# LM2596.net
KiCad netlist of a schematic drawn in Altium Designer
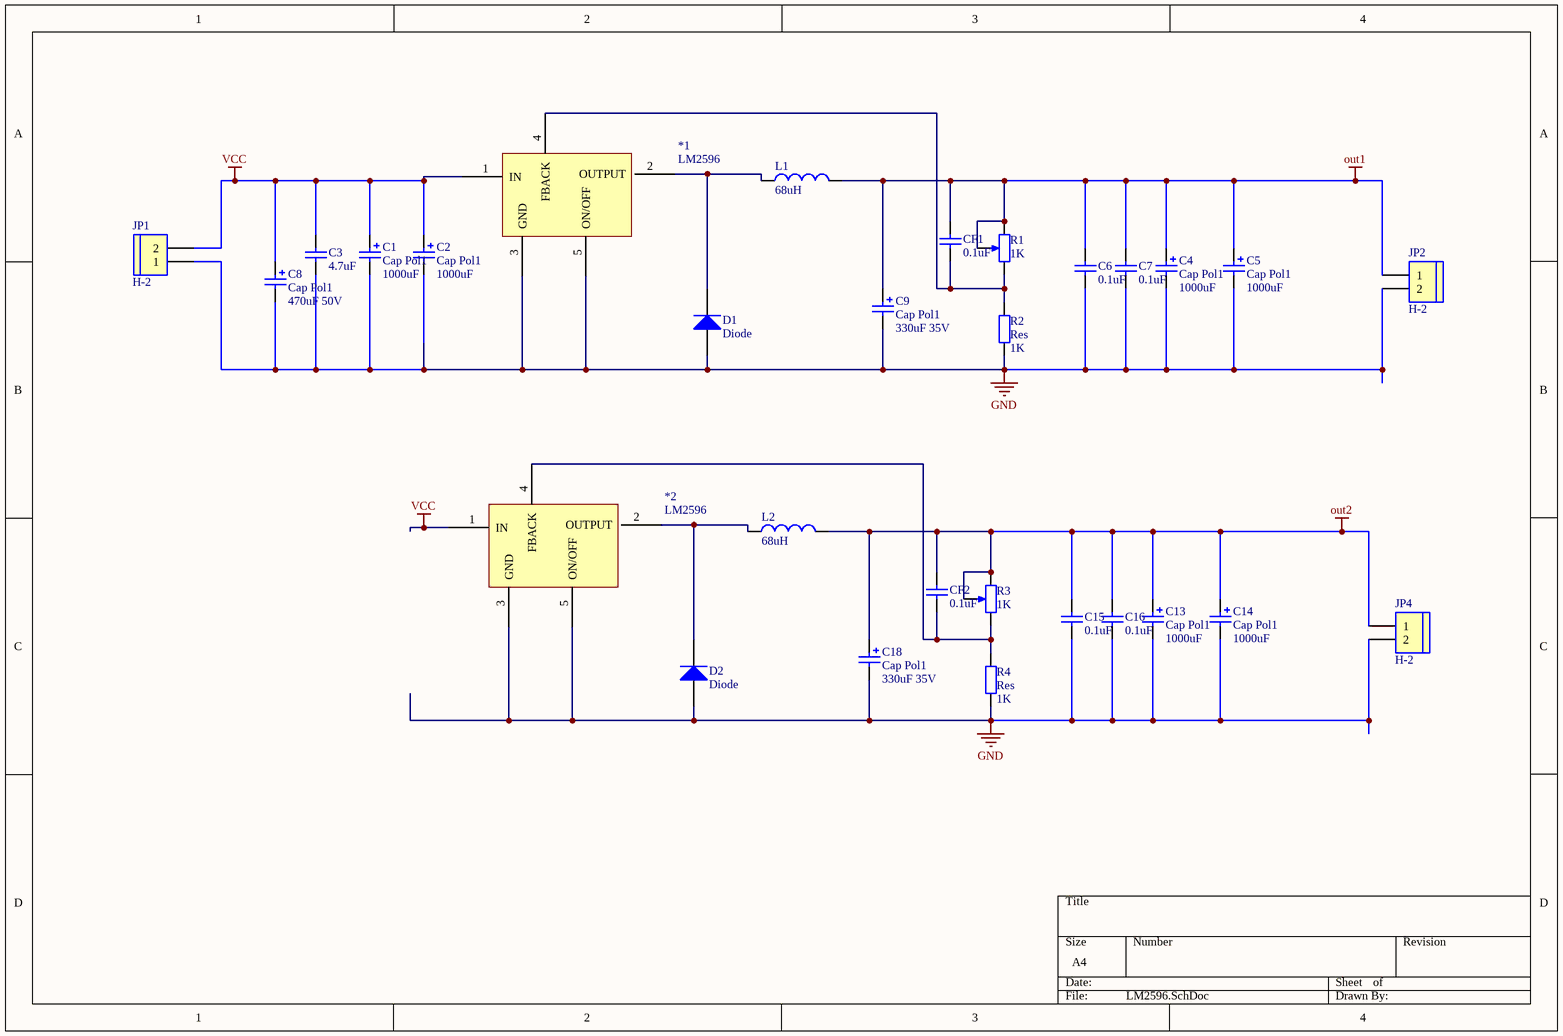
[diagram p0: LM2596.SchDoc]

(export (version "E")
  (design (tool "Eeschema 10.0.6"))
  (components
    (comp (ref "*1") (value "LM2596") (footprint "HDR1-5") (libsource (lib "HGH") (part "LM2596")))
    (comp (ref "*2") (value "LM2596") (footprint "HDR1-5") (libsource (lib "HGH") (part "LM2596")))
    (comp (ref "C1")
      (value "Cap Pol1")
      (footprint "RB0.3-0.65")
      (description "Polarized Capacitor (Radial)")
      (fields
        (field (name "MANUFACTURER") "Generic Components")
        (field (name "ALTIUM_VALUE") "1000uF")
        (field (name "PUBLISHER") "Altium Hobart Technology Centre")
      )
      (libsource (lib "HGH") (part "Cap Pol1"))
    )
    (comp (ref "C2")
      (value "Cap Pol1")
      (footprint "RB0.3-0.65")
      (description "Polarized Capacitor (Radial)")
      (fields
        (field (name "MANUFACTURER") "Generic Components")
        (field (name "ALTIUM_VALUE") "1000uF")
        (field (name "PUBLISHER") "Altium Hobart Technology Centre")
      )
      (libsource (lib "HGH") (part "Cap Pol1"))
    )
    (comp (ref "C3")
      (value "4.7uF")
      (footprint "CC1005-0402")
      (description "Capacitor")
      (fields
        (field (name "MANUFACTURER") "Generic Components")
        (field (name "Comment") "CAP")
        (field (name "PUBLISHER") "Altium Hobart Technology Centre")
      )
      (libsource (lib "HGH") (part "CAP"))
    )
    (comp (ref "C4")
      (value "Cap Pol1")
      (footprint "RB0.3-0.65")
      (description "Polarized Capacitor (Radial)")
      (fields
        (field (name "MANUFACTURER") "Generic Components")
        (field (name "ALTIUM_VALUE") "1000uF")
        (field (name "PUBLISHER") "Altium Hobart Technology Centre")
      )
      (libsource (lib "HGH") (part "Cap Pol1"))
    )
    (comp (ref "C5")
      (value "Cap Pol1")
      (footprint "RB0.3-0.65")
      (description "Polarized Capacitor (Radial)")
      (fields
        (field (name "MANUFACTURER") "Generic Components")
        (field (name "ALTIUM_VALUE") "1000uF")
        (field (name "PUBLISHER") "Altium Hobart Technology Centre")
      )
      (libsource (lib "HGH") (part "Cap Pol1"))
    )
    (comp (ref "C6")
      (value "0.1uF")
      (footprint "CC1005-0402")
      (description "Capacitor")
      (fields
        (field (name "MANUFACTURER") "Generic Components")
        (field (name "Comment") "CAP")
        (field (name "PUBLISHER") "Altium Hobart Technology Centre")
      )
      (libsource (lib "HGH") (part "CAP"))
    )
    (comp (ref "C7")
      (value "0.1uF")
      (footprint "CC1005-0402")
      (description "Capacitor")
      (fields
        (field (name "MANUFACTURER") "Generic Components")
        (field (name "Comment") "CAP")
        (field (name "PUBLISHER") "Altium Hobart Technology Centre")
      )
      (libsource (lib "HGH") (part "CAP"))
    )
    (comp (ref "C8")
      (value "Cap Pol1")
      (footprint "RB0.3-0.65")
      (description "Polarized Capacitor (Radial)")
      (fields
        (field (name "MANUFACTURER") "Generic Components")
        (field (name "ALTIUM_VALUE") "470uF 50V")
        (field (name "PUBLISHER") "Altium Hobart Technology Centre")
      )
      (libsource (lib "HGH") (part "Cap Pol1"))
    )
    (comp (ref "C9")
      (value "Cap Pol1")
      (footprint "RB0.3-0.65")
      (description "Polarized Capacitor (Radial)")
      (fields
        (field (name "MANUFACTURER") "Generic Components")
        (field (name "ALTIUM_VALUE") "330uF 35V")
        (field (name "PUBLISHER") "Altium Hobart Technology Centre")
      )
      (libsource (lib "HGH") (part "Cap Pol1"))
    )
    (comp (ref "C13")
      (value "Cap Pol1")
      (footprint "RB0.3-0.65")
      (description "Polarized Capacitor (Radial)")
      (fields
        (field (name "MANUFACTURER") "Generic Components")
        (field (name "ALTIUM_VALUE") "1000uF")
        (field (name "PUBLISHER") "Altium Hobart Technology Centre")
      )
      (libsource (lib "HGH") (part "Cap Pol1"))
    )
    (comp (ref "C14")
      (value "Cap Pol1")
      (footprint "RB0.3-0.65")
      (description "Polarized Capacitor (Radial)")
      (fields
        (field (name "MANUFACTURER") "Generic Components")
        (field (name "ALTIUM_VALUE") "1000uF")
        (field (name "PUBLISHER") "Altium Hobart Technology Centre")
      )
      (libsource (lib "HGH") (part "Cap Pol1"))
    )
    (comp (ref "C15")
      (value "0.1uF")
      (footprint "CC1005-0402")
      (description "Capacitor")
      (fields
        (field (name "MANUFACTURER") "Generic Components")
        (field (name "Comment") "CAP")
        (field (name "PUBLISHER") "Altium Hobart Technology Centre")
      )
      (libsource (lib "HGH") (part "CAP"))
    )
    (comp (ref "C16")
      (value "0.1uF")
      (footprint "CC1005-0402")
      (description "Capacitor")
      (fields
        (field (name "MANUFACTURER") "Generic Components")
        (field (name "Comment") "CAP")
        (field (name "PUBLISHER") "Altium Hobart Technology Centre")
      )
      (libsource (lib "HGH") (part "CAP"))
    )
    (comp (ref "C18")
      (value "Cap Pol1")
      (footprint "RB0.3-0.65")
      (description "Polarized Capacitor (Radial)")
      (fields
        (field (name "MANUFACTURER") "Generic Components")
        (field (name "ALTIUM_VALUE") "330uF 35V")
        (field (name "PUBLISHER") "Altium Hobart Technology Centre")
      )
      (libsource (lib "HGH") (part "Cap Pol1"))
    )
    (comp (ref "CF1")
      (value "0.1uF")
      (footprint "CC1005-0402")
      (description "Capacitor")
      (fields
        (field (name "MANUFACTURER") "Generic Components")
        (field (name "Comment") "CAP")
        (field (name "PUBLISHER") "Altium Hobart Technology Centre")
      )
      (libsource (lib "HGH") (part "CAP"))
    )
    (comp (ref "CF2")
      (value "0.1uF")
      (footprint "CC1005-0402")
      (description "Capacitor")
      (fields
        (field (name "MANUFACTURER") "Generic Components")
        (field (name "Comment") "CAP")
        (field (name "PUBLISHER") "Altium Hobart Technology Centre")
      )
      (libsource (lib "HGH") (part "CAP"))
    )
    (comp (ref "D1")
      (value "Diode")
      (footprint "Diode-5817")
      (description "Default Diode")
      (fields
        (field (name "MANUFACTURER") "Generic Components")
        (field (name "PUBLISHER") "Altium Hobart Technology Centre")
      )
      (libsource (lib "HGH") (part "Diode"))
    )
    (comp (ref "D2")
      (value "Diode")
      (footprint "Diode-5817")
      (description "Default Diode")
      (fields
        (field (name "MANUFACTURER") "Generic Components")
        (field (name "PUBLISHER") "Altium Hobart Technology Centre")
      )
      (libsource (lib "HGH") (part "Diode"))
    )
    (comp (ref "JP1")
      (value "H-2")
      (footprint "JP-2")
      (description "Header, 2-Pin")
      (fields (field (name "MANUFACTURER") "Generic Components"))
      (libsource (lib "") (part "H-2_1"))
    )
    (comp (ref "JP2")
      (value "H-2")
      (footprint "JP-2")
      (description "Header, 2-Pin")
      (fields (field (name "MANUFACTURER") "Generic Components"))
      (libsource (lib "HGH") (part "H-2"))
    )
    (comp (ref "JP4")
      (value "H-2")
      (footprint "JP-2")
      (description "Header, 2-Pin")
      (fields (field (name "MANUFACTURER") "Generic Components"))
      (libsource (lib "HGH") (part "H-2"))
    )
    (comp (ref "L1")
      (value "68uH")
      (footprint "RBL0.2")
      (description "Inductor")
      (fields
        (field (name "MANUFACTURER") "Generic Components")
        (field (name "Comment") "INDUCTOT")
        (field (name "PUBLISHER") "Altium Hobart Technology Centre")
      )
      (libsource (lib "HGH") (part "INDUCTOT"))
    )
    (comp (ref "L2")
      (value "68uH")
      (footprint "RBL0.2")
      (description "Inductor")
      (fields
        (field (name "MANUFACTURER") "Generic Components")
        (field (name "Comment") "INDUCTOT")
        (field (name "PUBLISHER") "Altium Hobart Technology Centre")
      )
      (libsource (lib "HGH") (part "INDUCTOT"))
    )
    (comp (ref "R1")
      (value "1K")
      (footprint "VR-S")
      (description "Potentiometer")
      (fields (field (name "Comment") "RES-Pot2"))
      (libsource (lib "HGH") (part "RES-Pot2"))
    )
    (comp (ref "R2")
      (value "Res")
      (footprint "1n4148")
      (description "Resistor")
      (fields
        (field (name "MANUFACTURER") "Generic Components")
        (field (name "ALTIUM_VALUE") "1K")
        (field (name "PUBLISHER") "Altium Hobart Technology Centre")
      )
      (libsource (lib "HGH") (part "Res"))
    )
    (comp (ref "R3")
      (value "1K")
      (footprint "VR-S")
      (description "Potentiometer")
      (fields (field (name "Comment") "RES-Pot2"))
      (libsource (lib "HGH") (part "RES-Pot2"))
    )
    (comp (ref "R4")
      (value "Res")
      (footprint "1n4148")
      (description "Resistor")
      (fields
        (field (name "MANUFACTURER") "Generic Components")
        (field (name "ALTIUM_VALUE") "1K")
        (field (name "PUBLISHER") "Altium Hobart Technology Centre")
      )
      (libsource (lib "HGH") (part "Res"))
    )
  )
  (nets
    (net (code "1") (name "GND") (class "Default")
      (node (ref "*1") (pin "3") (pinfunction "GND_3") (pintype "passive"))
      (node (ref "*1") (pin "5") (pinfunction "ON/OFF_5") (pintype "passive"))
      (node (ref "*2") (pin "3") (pinfunction "GND_3") (pintype "passive"))
      (node (ref "*2") (pin "5") (pinfunction "ON/OFF_5") (pintype "passive"))
      (node (ref "C1") (pin "2") (pinfunction "2_2") (pintype "passive"))
      (node (ref "C13") (pin "2") (pinfunction "2_2") (pintype "passive"))
      (node (ref "C14") (pin "2") (pinfunction "2_2") (pintype "passive"))
      (node (ref "C15") (pin "1") (pinfunction "1_1") (pintype "passive"))
      (node (ref "C16") (pin "1") (pinfunction "1_1") (pintype "passive"))
      (node (ref "C18") (pin "2") (pinfunction "2_2") (pintype "passive"))
      (node (ref "C2") (pin "2") (pinfunction "2_2") (pintype "passive"))
      (node (ref "C3") (pin "1") (pinfunction "1_1") (pintype "passive"))
      (node (ref "C4") (pin "2") (pinfunction "2_2") (pintype "passive"))
      (node (ref "C5") (pin "2") (pinfunction "2_2") (pintype "passive"))
      (node (ref "C6") (pin "1") (pinfunction "1_1") (pintype "passive"))
      (node (ref "C7") (pin "1") (pinfunction "1_1") (pintype "passive"))
      (node (ref "C8") (pin "2") (pinfunction "2_2") (pintype "passive"))
      (node (ref "C9") (pin "2") (pinfunction "2_2") (pintype "passive"))
      (node (ref "D1") (pin "1") (pinfunction "A_1") (pintype "passive"))
      (node (ref "D2") (pin "1") (pinfunction "A_1") (pintype "passive"))
      (node (ref "JP1") (pin "1") (pinfunction "1_1") (pintype "passive"))
      (node (ref "JP2") (pin "2") (pinfunction "2_2") (pintype "passive"))
      (node (ref "JP4") (pin "2") (pinfunction "2_2") (pintype "passive"))
      (node (ref "R2") (pin "1") (pinfunction "1_1") (pintype "passive"))
      (node (ref "R4") (pin "1") (pinfunction "1_1") (pintype "passive"))
    )
    (net (code "2") (name "Net-(*1-FBACK)") (class "Default")
      (node (ref "*1") (pin "4") (pinfunction "FBACK_4") (pintype "passive"))
      (node (ref "CF1") (pin "1") (pinfunction "1_1") (pintype "passive"))
      (node (ref "R1") (pin "1") (pinfunction "BOT_1") (pintype "passive"))
      (node (ref "R2") (pin "2") (pinfunction "2_2") (pintype "passive"))
    )
    (net (code "3") (name "Net-(*1-OUTPUT)") (class "Default")
      (node (ref "*1") (pin "2") (pinfunction "OUTPUT_2") (pintype "passive"))
      (node (ref "D1") (pin "2") (pinfunction "K_2") (pintype "passive"))
      (node (ref "L1") (pin "1") (pinfunction "1_1") (pintype "passive"))
    )
    (net (code "4") (name "Net-(*2-FBACK)") (class "Default")
      (node (ref "*2") (pin "4") (pinfunction "FBACK_4") (pintype "passive"))
      (node (ref "CF2") (pin "1") (pinfunction "1_1") (pintype "passive"))
      (node (ref "R3") (pin "1") (pinfunction "BOT_1") (pintype "passive"))
      (node (ref "R4") (pin "2") (pinfunction "2_2") (pintype "passive"))
    )
    (net (code "5") (name "Net-(*2-OUTPUT)") (class "Default")
      (node (ref "*2") (pin "2") (pinfunction "OUTPUT_2") (pintype "passive"))
      (node (ref "D2") (pin "2") (pinfunction "K_2") (pintype "passive"))
      (node (ref "L2") (pin "1") (pinfunction "1_1") (pintype "passive"))
    )
    (net (code "6") (name "VCC") (class "Default")
      (node (ref "*1") (pin "1") (pinfunction "IN_1") (pintype "passive"))
      (node (ref "*2") (pin "1") (pinfunction "IN_1") (pintype "passive"))
      (node (ref "C1") (pin "1") (pinfunction "1_1") (pintype "passive"))
      (node (ref "C2") (pin "1") (pinfunction "1_1") (pintype "passive"))
      (node (ref "C3") (pin "2") (pinfunction "2_2") (pintype "passive"))
      (node (ref "C8") (pin "1") (pinfunction "1_1") (pintype "passive"))
      (node (ref "JP1") (pin "2") (pinfunction "2_2") (pintype "passive"))
    )
    (net (code "7") (name "out1") (class "Default")
      (node (ref "C4") (pin "1") (pinfunction "1_1") (pintype "passive"))
      (node (ref "C5") (pin "1") (pinfunction "1_1") (pintype "passive"))
      (node (ref "C6") (pin "2") (pinfunction "2_2") (pintype "passive"))
      (node (ref "C7") (pin "2") (pinfunction "2_2") (pintype "passive"))
      (node (ref "C9") (pin "1") (pinfunction "1_1") (pintype "passive"))
      (node (ref "CF1") (pin "2") (pinfunction "2_2") (pintype "passive"))
      (node (ref "JP2") (pin "1") (pinfunction "1_1") (pintype "passive"))
      (node (ref "L1") (pin "2") (pinfunction "2_2") (pintype "passive"))
      (node (ref "R1") (pin "2") (pinfunction "TAP_2") (pintype "passive"))
      (node (ref "R1") (pin "3") (pinfunction "TOP_3") (pintype "passive"))
    )
    (net (code "8") (name "out2") (class "Default")
      (node (ref "C13") (pin "1") (pinfunction "1_1") (pintype "passive"))
      (node (ref "C14") (pin "1") (pinfunction "1_1") (pintype "passive"))
      (node (ref "C15") (pin "2") (pinfunction "2_2") (pintype "passive"))
      (node (ref "C16") (pin "2") (pinfunction "2_2") (pintype "passive"))
      (node (ref "C18") (pin "1") (pinfunction "1_1") (pintype "passive"))
      (node (ref "CF2") (pin "2") (pinfunction "2_2") (pintype "passive"))
      (node (ref "JP4") (pin "1") (pinfunction "1_1") (pintype "passive"))
      (node (ref "L2") (pin "2") (pinfunction "2_2") (pintype "passive"))
      (node (ref "R3") (pin "2") (pinfunction "TAP_2") (pintype "passive"))
      (node (ref "R3") (pin "3") (pinfunction "TOP_3") (pintype "passive"))
    )
  )
)
